# PICKIT4-adaptorar.net
KiCad netlist of a schematic drawn in EAGLE
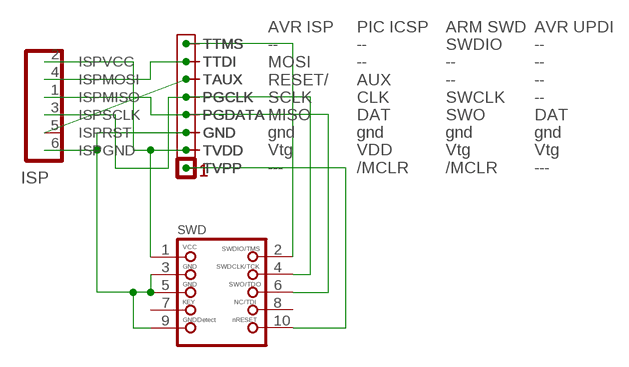
[diagram p0: schematic, sheet 1]

(export (version "E")
  (design (tool "Eeschema 10.0.6"))
  (components
    (comp (ref "ISP")
      (value "AVR-ISP")
      (footprint "eagle-import:6PINS")
      (libsource (lib "eagle-import") (part "AVR-ISP"))
    )
    (comp (ref "SWD")
      (value "JTAG-CORTEXM3")
      (footprint "eagle-import:2X05_1.27MM_SMT")
      (libsource (lib "eagle-import") (part "JTAG-CORTEXM3"))
    )
    (comp (ref "U$1")
      (value "PICKIT4PINHDR")
      (footprint "eagle-import:PINHEAD1X8")
      (libsource (lib "eagle-import") (part "PICKIT4PINHDR"))
    )
    (comp (ref "U$3")
      (value "PICKIT4PINHDR")
      (footprint "eagle-import:PINHEAD1X8")
      (libsource (lib "eagle-import") (part "PICKIT4PINHDR"))
    )
    (comp (ref "U$4")
      (value "PICKIT4PINHDR")
      (footprint "eagle-import:PINHEAD1X8")
      (libsource (lib "eagle-import") (part "PICKIT4PINHDR"))
    )
  )
  (nets
    (net (code "1") (name "Net-(ISP-ISPGND)") (class "Default")
      (node (ref "ISP") (pin "6") (pinfunction "ISPGND_6") (pintype "power_in"))
      (node (ref "SWD") (pin "3") (pinfunction "3_3") (pintype "passive"))
      (node (ref "SWD") (pin "5") (pinfunction "5_5") (pintype "passive"))
      (node (ref "SWD") (pin "9") (pinfunction "9_9") (pintype "passive"))
      (node (ref "U$1") (pin "P$3") (pinfunction "GND_P$3") (pintype "power_in"))
      (node (ref "U$3") (pin "P$3") (pinfunction "GND_P$3") (pintype "power_in"))
      (node (ref "U$4") (pin "P$3") (pinfunction "GND_P$3") (pintype "power_in"))
    )
    (net (code "2") (name "Net-(ISP-ISPMISO)") (class "Default")
      (node (ref "ISP") (pin "1") (pinfunction "ISPMISO_1") (pintype "input"))
      (node (ref "SWD") (pin "6") (pinfunction "6_6") (pintype "passive"))
      (node (ref "U$1") (pin "P$4") (pinfunction "PGDATA_P$4") (pintype "bidirectional"))
      (node (ref "U$3") (pin "P$4") (pinfunction "PGDATA_P$4") (pintype "bidirectional"))
      (node (ref "U$4") (pin "P$4") (pinfunction "PGDATA_P$4") (pintype "bidirectional"))
    )
    (net (code "3") (name "Net-(ISP-ISPMOSI)") (class "Default")
      (node (ref "ISP") (pin "4") (pinfunction "ISPMOSI_4") (pintype "output"))
      (node (ref "U$1") (pin "P$7") (pinfunction "TTDI_P$7") (pintype "bidirectional"))
      (node (ref "U$3") (pin "P$7") (pinfunction "TTDI_P$7") (pintype "bidirectional"))
      (node (ref "U$4") (pin "P$7") (pinfunction "TTDI_P$7") (pintype "bidirectional"))
    )
    (net (code "4") (name "Net-(ISP-ISPRST)") (class "Default")
      (node (ref "ISP") (pin "5") (pinfunction "ISPRST_5") (pintype "input"))
      (node (ref "U$1") (pin "P$6") (pinfunction "TAUX_P$6") (pintype "bidirectional"))
      (node (ref "U$3") (pin "P$6") (pinfunction "TAUX_P$6") (pintype "bidirectional"))
      (node (ref "U$4") (pin "P$6") (pinfunction "TAUX_P$6") (pintype "bidirectional"))
    )
    (net (code "5") (name "Net-(ISP-ISPSCLK)") (class "Default")
      (node (ref "ISP") (pin "3") (pinfunction "ISPSCLK_3") (pintype "output"))
      (node (ref "SWD") (pin "4") (pinfunction "4_4") (pintype "passive"))
      (node (ref "U$1") (pin "P$5") (pinfunction "PGCLK_P$5") (pintype "bidirectional"))
      (node (ref "U$3") (pin "P$5") (pinfunction "PGCLK_P$5") (pintype "bidirectional"))
      (node (ref "U$4") (pin "P$5") (pinfunction "PGCLK_P$5") (pintype "bidirectional"))
    )
    (net (code "6") (name "Net-(ISP-ISPVCC)") (class "Default")
      (node (ref "ISP") (pin "2") (pinfunction "ISPVCC_2") (pintype "power_in"))
      (node (ref "SWD") (pin "1") (pinfunction "1_1") (pintype "passive"))
      (node (ref "U$1") (pin "P$2") (pinfunction "TVDD_P$2") (pintype "bidirectional"))
      (node (ref "U$3") (pin "P$2") (pinfunction "TVDD_P$2") (pintype "bidirectional"))
      (node (ref "U$4") (pin "P$2") (pinfunction "TVDD_P$2") (pintype "bidirectional"))
    )
    (net (code "7") (name "Net-(U$1A-TTMS)") (class "Default")
      (node (ref "SWD") (pin "2") (pinfunction "2_2") (pintype "passive"))
      (node (ref "U$1") (pin "P$8") (pinfunction "TTMS_P$8") (pintype "bidirectional"))
      (node (ref "U$3") (pin "P$8") (pinfunction "TTMS_P$8") (pintype "bidirectional"))
      (node (ref "U$4") (pin "P$8") (pinfunction "TTMS_P$8") (pintype "bidirectional"))
    )
    (net (code "8") (name "Net-(U$1A-TVPP)") (class "Default")
      (node (ref "SWD") (pin "10") (pinfunction "10_10") (pintype "passive"))
      (node (ref "U$1") (pin "P$1") (pinfunction "TVPP_P$1") (pintype "bidirectional"))
      (node (ref "U$3") (pin "P$1") (pinfunction "TVPP_P$1") (pintype "bidirectional"))
      (node (ref "U$4") (pin "P$1") (pinfunction "TVPP_P$1") (pintype "bidirectional"))
    )
    (net (code "9") (name "unconnected-(SWD-Pad7)") (class "Default")
      (node (ref "SWD") (pin "7") (pinfunction "7_7") (pintype "passive"))
    )
    (net (code "10") (name "unconnected-(SWD-Pad8)") (class "Default")
      (node (ref "SWD") (pin "8") (pinfunction "8_8") (pintype "passive"))
    )
  )
)
